# ui_sdram.net
KiCad netlist of a schematic drawn in Altium Designer
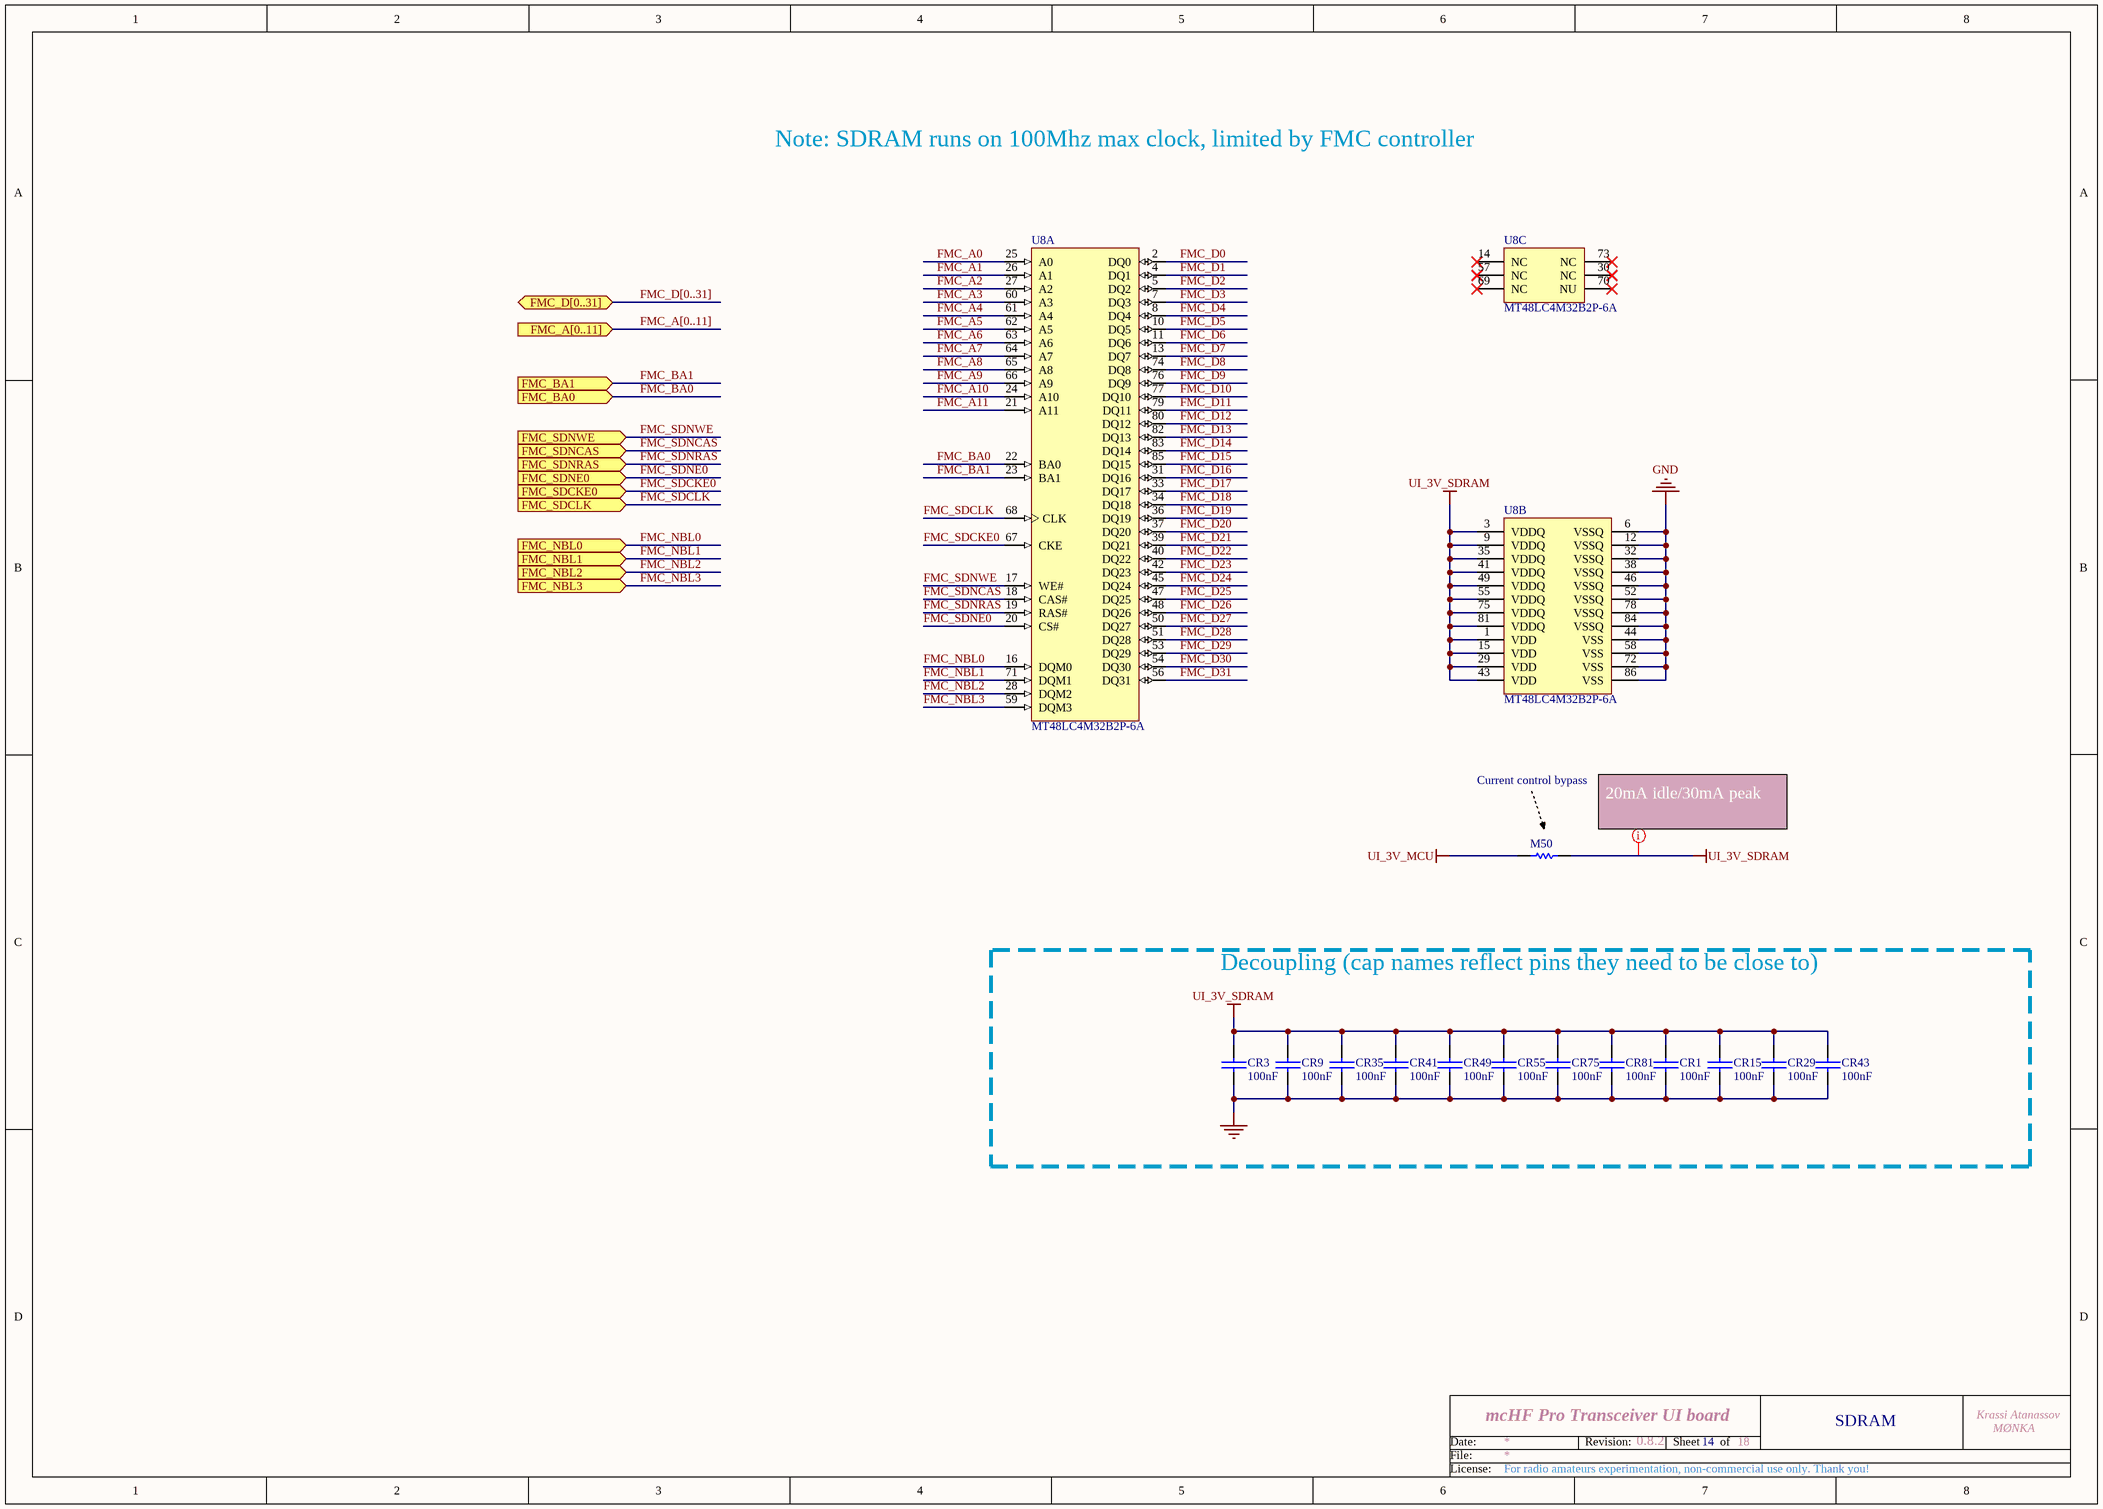
[diagram p0: ui_sdram.SchDoc]

(export (version "E")
  (design (tool "Eeschema 10.0.6"))
  (components
    (comp (ref "CR1")
      (value "100nF")
      (footprint "0805")
      (description "Capacitor")
      (libsource (lib "mcHF_ui") (part "CAP"))
    )
    (comp (ref "CR3")
      (value "100nF")
      (footprint "0805")
      (description "Capacitor")
      (libsource (lib "mcHF_ui") (part "CAP"))
    )
    (comp (ref "CR9")
      (value "100nF")
      (footprint "0805")
      (description "Capacitor")
      (libsource (lib "mcHF_ui") (part "CAP"))
    )
    (comp (ref "CR15")
      (value "100nF")
      (footprint "0805")
      (description "Capacitor")
      (libsource (lib "mcHF_ui") (part "CAP"))
    )
    (comp (ref "CR29")
      (value "100nF")
      (footprint "0805")
      (description "Capacitor")
      (libsource (lib "mcHF_ui") (part "CAP"))
    )
    (comp (ref "CR35")
      (value "100nF")
      (footprint "0805")
      (description "Capacitor")
      (libsource (lib "mcHF_ui") (part "CAP"))
    )
    (comp (ref "CR41")
      (value "100nF")
      (footprint "0805")
      (description "Capacitor")
      (libsource (lib "mcHF_ui") (part "CAP"))
    )
    (comp (ref "CR43")
      (value "100nF")
      (footprint "0805")
      (description "Capacitor")
      (libsource (lib "mcHF_ui") (part "CAP"))
    )
    (comp (ref "CR49")
      (value "100nF")
      (footprint "0805")
      (description "Capacitor")
      (libsource (lib "mcHF_ui") (part "CAP"))
    )
    (comp (ref "CR55")
      (value "100nF")
      (footprint "0805")
      (description "Capacitor")
      (libsource (lib "mcHF_ui") (part "CAP"))
    )
    (comp (ref "CR75")
      (value "100nF")
      (footprint "0805")
      (description "Capacitor")
      (libsource (lib "mcHF_ui") (part "CAP"))
    )
    (comp (ref "CR81")
      (value "100nF")
      (footprint "0805")
      (description "Capacitor")
      (libsource (lib "mcHF_ui") (part "CAP"))
    )
    (comp (ref "M50")
      (value "0")
      (footprint "SB_0603")
      (description "Link")
      (fields (field (name "PUBLISHER") "Altium Limited"))
      (libsource (lib "__ui") (part "Link"))
    )
    (comp (ref "U8")
      (value "MT48LC4M32B2P-6A")
      (footprint "MICT-TG-86_N")
      (description "128Mb PC133 SDR SDRAM, 4Mb x 32, 6ns, 3.3V, 0 to 70 degC, 86-Pin TSOP")
      (libsource (lib "mcHFpro_logic") (part "MT48LC4M32B2P-6A"))
    )
  )
  (nets
    (net (code "1") (name "/FMC_A0") (class "Default")
      (node (ref "U8") (pin "25") (pinfunction "A0_25") (pintype "input"))
    )
    (net (code "2") (name "/FMC_A1") (class "Default")
      (node (ref "U8") (pin "26") (pinfunction "A1_26") (pintype "input"))
    )
    (net (code "3") (name "/FMC_A2") (class "Default")
      (node (ref "U8") (pin "27") (pinfunction "A2_27") (pintype "input"))
    )
    (net (code "4") (name "/FMC_A3") (class "Default")
      (node (ref "U8") (pin "60") (pinfunction "A3_60") (pintype "input"))
    )
    (net (code "5") (name "/FMC_A4") (class "Default")
      (node (ref "U8") (pin "61") (pinfunction "A4_61") (pintype "input"))
    )
    (net (code "6") (name "/FMC_A5") (class "Default")
      (node (ref "U8") (pin "62") (pinfunction "A5_62") (pintype "input"))
    )
    (net (code "7") (name "/FMC_A6") (class "Default")
      (node (ref "U8") (pin "63") (pinfunction "A6_63") (pintype "input"))
    )
    (net (code "8") (name "/FMC_A7") (class "Default")
      (node (ref "U8") (pin "64") (pinfunction "A7_64") (pintype "input"))
    )
    (net (code "9") (name "/FMC_A8") (class "Default")
      (node (ref "U8") (pin "65") (pinfunction "A8_65") (pintype "input"))
    )
    (net (code "10") (name "/FMC_A9") (class "Default")
      (node (ref "U8") (pin "66") (pinfunction "A9_66") (pintype "input"))
    )
    (net (code "11") (name "/FMC_A10") (class "Default")
      (node (ref "U8") (pin "24") (pinfunction "A10_24") (pintype "input"))
    )
    (net (code "12") (name "/FMC_A11") (class "Default")
      (node (ref "U8") (pin "21") (pinfunction "A11_21") (pintype "input"))
    )
    (net (code "14") (name "/FMC_BA0") (class "Default")
      (node (ref "U8") (pin "22") (pinfunction "BA0_22") (pintype "input"))
    )
    (net (code "15") (name "/FMC_BA1") (class "Default")
      (node (ref "U8") (pin "23") (pinfunction "BA1_23") (pintype "input"))
    )
    (net (code "16") (name "/FMC_D0") (class "Default")
      (node (ref "U8") (pin "2") (pinfunction "DQ0_2") (pintype "bidirectional"))
    )
    (net (code "17") (name "/FMC_D1") (class "Default")
      (node (ref "U8") (pin "4") (pinfunction "DQ1_4") (pintype "bidirectional"))
    )
    (net (code "18") (name "/FMC_D2") (class "Default")
      (node (ref "U8") (pin "5") (pinfunction "DQ2_5") (pintype "bidirectional"))
    )
    (net (code "19") (name "/FMC_D3") (class "Default")
      (node (ref "U8") (pin "7") (pinfunction "DQ3_7") (pintype "bidirectional"))
    )
    (net (code "20") (name "/FMC_D4") (class "Default")
      (node (ref "U8") (pin "8") (pinfunction "DQ4_8") (pintype "bidirectional"))
    )
    (net (code "21") (name "/FMC_D5") (class "Default")
      (node (ref "U8") (pin "10") (pinfunction "DQ5_10") (pintype "bidirectional"))
    )
    (net (code "22") (name "/FMC_D6") (class "Default")
      (node (ref "U8") (pin "11") (pinfunction "DQ6_11") (pintype "bidirectional"))
    )
    (net (code "23") (name "/FMC_D7") (class "Default")
      (node (ref "U8") (pin "13") (pinfunction "DQ7_13") (pintype "bidirectional"))
    )
    (net (code "24") (name "/FMC_D8") (class "Default")
      (node (ref "U8") (pin "74") (pinfunction "DQ8_74") (pintype "bidirectional"))
    )
    (net (code "25") (name "/FMC_D9") (class "Default")
      (node (ref "U8") (pin "76") (pinfunction "DQ9_76") (pintype "bidirectional"))
    )
    (net (code "26") (name "/FMC_D10") (class "Default")
      (node (ref "U8") (pin "77") (pinfunction "DQ10_77") (pintype "bidirectional"))
    )
    (net (code "27") (name "/FMC_D11") (class "Default")
      (node (ref "U8") (pin "79") (pinfunction "DQ11_79") (pintype "bidirectional"))
    )
    (net (code "28") (name "/FMC_D12") (class "Default")
      (node (ref "U8") (pin "80") (pinfunction "DQ12_80") (pintype "bidirectional"))
    )
    (net (code "29") (name "/FMC_D13") (class "Default")
      (node (ref "U8") (pin "82") (pinfunction "DQ13_82") (pintype "bidirectional"))
    )
    (net (code "30") (name "/FMC_D14") (class "Default")
      (node (ref "U8") (pin "83") (pinfunction "DQ14_83") (pintype "bidirectional"))
    )
    (net (code "31") (name "/FMC_D15") (class "Default")
      (node (ref "U8") (pin "85") (pinfunction "DQ15_85") (pintype "bidirectional"))
    )
    (net (code "32") (name "/FMC_D16") (class "Default")
      (node (ref "U8") (pin "31") (pinfunction "DQ16_31") (pintype "bidirectional"))
    )
    (net (code "33") (name "/FMC_D17") (class "Default")
      (node (ref "U8") (pin "33") (pinfunction "DQ17_33") (pintype "bidirectional"))
    )
    (net (code "34") (name "/FMC_D18") (class "Default")
      (node (ref "U8") (pin "34") (pinfunction "DQ18_34") (pintype "bidirectional"))
    )
    (net (code "35") (name "/FMC_D19") (class "Default")
      (node (ref "U8") (pin "36") (pinfunction "DQ19_36") (pintype "bidirectional"))
    )
    (net (code "36") (name "/FMC_D20") (class "Default")
      (node (ref "U8") (pin "37") (pinfunction "DQ20_37") (pintype "bidirectional"))
    )
    (net (code "37") (name "/FMC_D21") (class "Default")
      (node (ref "U8") (pin "39") (pinfunction "DQ21_39") (pintype "bidirectional"))
    )
    (net (code "38") (name "/FMC_D22") (class "Default")
      (node (ref "U8") (pin "40") (pinfunction "DQ22_40") (pintype "bidirectional"))
    )
    (net (code "39") (name "/FMC_D23") (class "Default")
      (node (ref "U8") (pin "42") (pinfunction "DQ23_42") (pintype "bidirectional"))
    )
    (net (code "40") (name "/FMC_D24") (class "Default")
      (node (ref "U8") (pin "45") (pinfunction "DQ24_45") (pintype "bidirectional"))
    )
    (net (code "41") (name "/FMC_D25") (class "Default")
      (node (ref "U8") (pin "47") (pinfunction "DQ25_47") (pintype "bidirectional"))
    )
    (net (code "42") (name "/FMC_D26") (class "Default")
      (node (ref "U8") (pin "48") (pinfunction "DQ26_48") (pintype "bidirectional"))
    )
    (net (code "43") (name "/FMC_D27") (class "Default")
      (node (ref "U8") (pin "50") (pinfunction "DQ27_50") (pintype "bidirectional"))
    )
    (net (code "44") (name "/FMC_D28") (class "Default")
      (node (ref "U8") (pin "51") (pinfunction "DQ28_51") (pintype "bidirectional"))
    )
    (net (code "45") (name "/FMC_D29") (class "Default")
      (node (ref "U8") (pin "53") (pinfunction "DQ29_53") (pintype "bidirectional"))
    )
    (net (code "46") (name "/FMC_D30") (class "Default")
      (node (ref "U8") (pin "54") (pinfunction "DQ30_54") (pintype "bidirectional"))
    )
    (net (code "47") (name "/FMC_D31") (class "Default")
      (node (ref "U8") (pin "56") (pinfunction "DQ31_56") (pintype "bidirectional"))
    )
    (net (code "49") (name "/FMC_NBL0") (class "Default")
      (node (ref "U8") (pin "16") (pinfunction "DQM0_16") (pintype "input"))
    )
    (net (code "50") (name "/FMC_NBL1") (class "Default")
      (node (ref "U8") (pin "71") (pinfunction "DQM1_71") (pintype "input"))
    )
    (net (code "51") (name "/FMC_NBL2") (class "Default")
      (node (ref "U8") (pin "28") (pinfunction "DQM2_28") (pintype "input"))
    )
    (net (code "52") (name "/FMC_NBL3") (class "Default")
      (node (ref "U8") (pin "59") (pinfunction "DQM3_59") (pintype "input"))
    )
    (net (code "53") (name "/FMC_SDCKE0") (class "Default")
      (node (ref "U8") (pin "67") (pinfunction "CKE_67") (pintype "input"))
    )
    (net (code "54") (name "/FMC_SDCLK") (class "Default")
      (node (ref "U8") (pin "68") (pinfunction "CLK_68") (pintype "input"))
    )
    (net (code "55") (name "/FMC_SDNCAS") (class "Default")
      (node (ref "U8") (pin "18") (pinfunction "CAS#_18") (pintype "input"))
    )
    (net (code "56") (name "/FMC_SDNE0") (class "Default")
      (node (ref "U8") (pin "20") (pinfunction "CS#_20") (pintype "input"))
    )
    (net (code "57") (name "/FMC_SDNRAS") (class "Default")
      (node (ref "U8") (pin "19") (pinfunction "RAS#_19") (pintype "input"))
    )
    (net (code "58") (name "/FMC_SDNWE") (class "Default")
      (node (ref "U8") (pin "17") (pinfunction "WE#_17") (pintype "input"))
    )
    (net (code "59") (name "GND") (class "Default")
      (node (ref "CR1") (pin "2") (pinfunction "2_2") (pintype "passive"))
      (node (ref "CR15") (pin "2") (pinfunction "2_2") (pintype "passive"))
      (node (ref "CR29") (pin "2") (pinfunction "2_2") (pintype "passive"))
      (node (ref "CR3") (pin "2") (pinfunction "2_2") (pintype "passive"))
      (node (ref "CR35") (pin "2") (pinfunction "2_2") (pintype "passive"))
      (node (ref "CR41") (pin "2") (pinfunction "2_2") (pintype "passive"))
      (node (ref "CR43") (pin "2") (pinfunction "2_2") (pintype "passive"))
      (node (ref "CR49") (pin "2") (pinfunction "2_2") (pintype "passive"))
      (node (ref "CR55") (pin "2") (pinfunction "2_2") (pintype "passive"))
      (node (ref "CR75") (pin "2") (pinfunction "2_2") (pintype "passive"))
      (node (ref "CR81") (pin "2") (pinfunction "2_2") (pintype "passive"))
      (node (ref "CR9") (pin "2") (pinfunction "2_2") (pintype "passive"))
      (node (ref "U8") (pin "12") (pinfunction "VSSQ_12") (pintype "passive"))
      (node (ref "U8") (pin "32") (pinfunction "VSSQ_32") (pintype "passive"))
      (node (ref "U8") (pin "38") (pinfunction "VSSQ_38") (pintype "passive"))
      (node (ref "U8") (pin "44") (pinfunction "VSS_44") (pintype "passive"))
      (node (ref "U8") (pin "46") (pinfunction "VSSQ_46") (pintype "passive"))
      (node (ref "U8") (pin "52") (pinfunction "VSSQ_52") (pintype "passive"))
      (node (ref "U8") (pin "58") (pinfunction "VSS_58") (pintype "passive"))
      (node (ref "U8") (pin "6") (pinfunction "VSSQ_6") (pintype "passive"))
      (node (ref "U8") (pin "72") (pinfunction "VSS_72") (pintype "passive"))
      (node (ref "U8") (pin "78") (pinfunction "VSSQ_78") (pintype "passive"))
      (node (ref "U8") (pin "84") (pinfunction "VSSQ_84") (pintype "passive"))
      (node (ref "U8") (pin "86") (pinfunction "VSS_86") (pintype "passive"))
    )
    (net (code "60") (name "UI_3V_MCU") (class "Default")
      (node (ref "M50") (pin "1") (pinfunction "1_1") (pintype "passive"))
    )
    (net (code "61") (name "UI_3V_SDRAM") (class "Default")
      (node (ref "CR1") (pin "1") (pinfunction "1_1") (pintype "passive"))
      (node (ref "CR15") (pin "1") (pinfunction "1_1") (pintype "passive"))
      (node (ref "CR29") (pin "1") (pinfunction "1_1") (pintype "passive"))
      (node (ref "CR3") (pin "1") (pinfunction "1_1") (pintype "passive"))
      (node (ref "CR35") (pin "1") (pinfunction "1_1") (pintype "passive"))
      (node (ref "CR41") (pin "1") (pinfunction "1_1") (pintype "passive"))
      (node (ref "CR43") (pin "1") (pinfunction "1_1") (pintype "passive"))
      (node (ref "CR49") (pin "1") (pinfunction "1_1") (pintype "passive"))
      (node (ref "CR55") (pin "1") (pinfunction "1_1") (pintype "passive"))
      (node (ref "CR75") (pin "1") (pinfunction "1_1") (pintype "passive"))
      (node (ref "CR81") (pin "1") (pinfunction "1_1") (pintype "passive"))
      (node (ref "CR9") (pin "1") (pinfunction "1_1") (pintype "passive"))
      (node (ref "M50") (pin "2") (pinfunction "2_2") (pintype "passive"))
      (node (ref "U8") (pin "1") (pinfunction "VDD_1") (pintype "power_in"))
      (node (ref "U8") (pin "15") (pinfunction "VDD_15") (pintype "power_in"))
      (node (ref "U8") (pin "29") (pinfunction "VDD_29") (pintype "power_in"))
      (node (ref "U8") (pin "3") (pinfunction "VDDQ_3") (pintype "power_in"))
      (node (ref "U8") (pin "35") (pinfunction "VDDQ_35") (pintype "power_in"))
      (node (ref "U8") (pin "41") (pinfunction "VDDQ_41") (pintype "power_in"))
      (node (ref "U8") (pin "43") (pinfunction "VDD_43") (pintype "power_in"))
      (node (ref "U8") (pin "49") (pinfunction "VDDQ_49") (pintype "power_in"))
      (node (ref "U8") (pin "55") (pinfunction "VDDQ_55") (pintype "power_in"))
      (node (ref "U8") (pin "75") (pinfunction "VDDQ_75") (pintype "power_in"))
      (node (ref "U8") (pin "81") (pinfunction "VDDQ_81") (pintype "power_in"))
      (node (ref "U8") (pin "9") (pinfunction "VDDQ_9") (pintype "power_in"))
    )
    (net (code "62") (name "unconnected-(U8C-NC-Pad14)") (class "Default")
      (node (ref "U8") (pin "14") (pinfunction "NC_14") (pintype "passive+no_connect"))
    )
    (net (code "63") (name "unconnected-(U8C-NC-Pad30)") (class "Default")
      (node (ref "U8") (pin "30") (pinfunction "NC_30") (pintype "passive+no_connect"))
    )
    (net (code "64") (name "unconnected-(U8C-NC-Pad57)") (class "Default")
      (node (ref "U8") (pin "57") (pinfunction "NC_57") (pintype "passive+no_connect"))
    )
    (net (code "65") (name "unconnected-(U8C-NC-Pad69)") (class "Default")
      (node (ref "U8") (pin "69") (pinfunction "NC_69") (pintype "passive+no_connect"))
    )
    (net (code "66") (name "unconnected-(U8C-NC-Pad73)") (class "Default")
      (node (ref "U8") (pin "73") (pinfunction "NC_73") (pintype "passive+no_connect"))
    )
    (net (code "67") (name "unconnected-(U8C-NU-Pad70)") (class "Default")
      (node (ref "U8") (pin "70") (pinfunction "NU_70") (pintype "passive+no_connect"))
    )
  )
)
